# LedDimming.net
KiCad netlist of a schematic drawn in Altium Designer
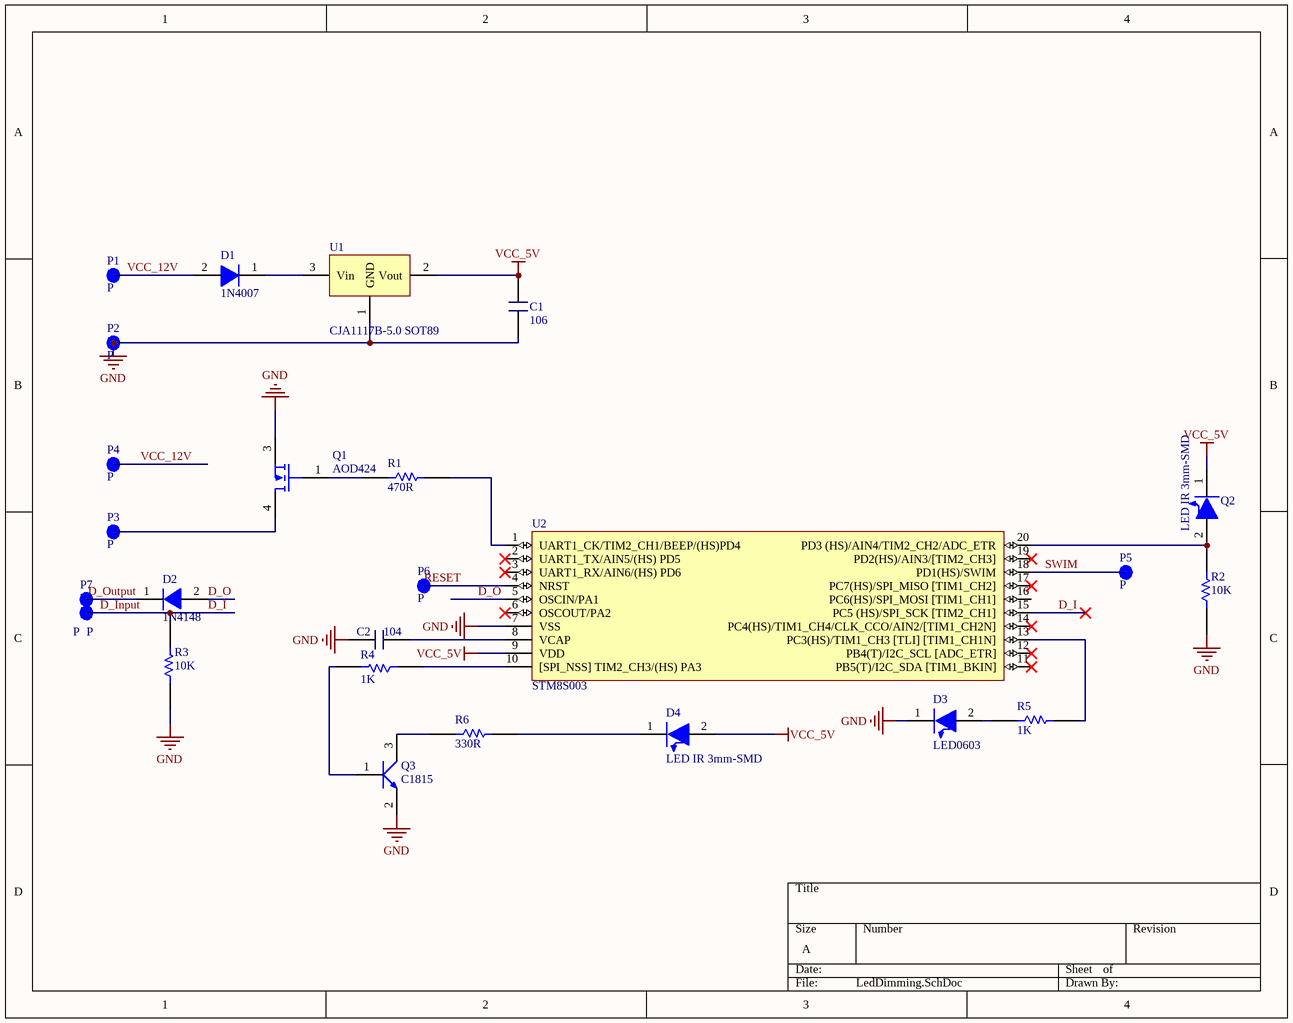
[diagram p0: LedDimming.SchDoc]

(export (version "E")
  (design (tool "Eeschema 10.0.6"))
  (components
    (comp (ref "C1")
      (value "106")
      (footprint "CAPC2012X12N")
      (libsource (lib "Integrated_Library1") (part "Capacitor 106"))
    )
    (comp (ref "C2")
      (value "104")
      (footprint "CAPC2012X12N")
      (libsource (lib "Integrated_Library1") (part "Capacitor 104 0603"))
    )
    (comp (ref "D1")
      (value "1N4007")
      (footprint "SODFL504X244-2N")
      (description "1N4007_SMD")
      (libsource (lib "Integrated_Library1") (part "1N4007_SMD Diode"))
    )
    (comp (ref "D2")
      (value "1N4148")
      (footprint "DIOMELF3515N")
      (description "DIODE GEN PURP 75V 200MA DO213AA")
      (libsource (lib "Integrated_Library1") (part "1N4148_SMD"))
    )
    (comp (ref "D3")
      (value "LED0603")
      (footprint "DIOC1608X06N")
      (libsource (lib "Integrated_Library1") (part "LED0603"))
    )
    (comp (ref "D4")
      (value "LED IR 3mm-SMD")
      (footprint "LED_IR_3mm-SMD")
      (libsource (lib "Integrated_Library1") (part "LED IR 3mm-SMD"))
    )
    (comp (ref "P1") (value "P") (footprint "Point") (libsource (lib "Integrated_Library1") (part "Point")))
    (comp (ref "P2") (value "P") (footprint "Point") (libsource (lib "Integrated_Library1") (part "Point")))
    (comp (ref "P3") (value "P") (footprint "Point") (libsource (lib "Integrated_Library1") (part "Point")))
    (comp (ref "P4") (value "P") (footprint "Point") (libsource (lib "Integrated_Library1") (part "Point")))
    (comp (ref "P5") (value "P") (footprint "Point") (libsource (lib "Integrated_Library1") (part "Point")))
    (comp (ref "P6") (value "P") (footprint "Point") (libsource (lib "Integrated_Library1") (part "Point")))
    (comp (ref "P7") (value "P") (footprint "Point") (libsource (lib "Integrated_Library1") (part "Point")))
    (comp (ref "P8") (value "P") (footprint "Point") (libsource (lib "Integrated_Library1") (part "Point")))
    (comp (ref "Q1")
      (value "AOD424")
      (footprint "DPAK228P991X229-3N_TO252")
      (description "AOD424 20V N-Channel MOSFET")
      (libsource (lib "Integrated_Library1") (part "AOD424 20V N-Channel MOSFET"))
    )
    (comp (ref "Q2")
      (value "LED IR 3mm-SMD")
      (footprint "LED_IR_3mm-SMD")
      (libsource (lib "Integrated_Library1") (part "LED IR 3mm-SMD"))
    )
    (comp (ref "Q3")
      (value "C1815")
      (footprint "SOT95P278X125-3N")
      (description "SOT-23 Plastic-Encapsulate Transistors")
      (libsource (lib "Integrated_Library1") (part "Transitor C1815 NPN"))
    )
    (comp (ref "R1")
      (value "470R")
      (footprint "RESC2608X06N_0603")
      (description "Thick Film Resistors - SMD 470 ohm 5%")
      (libsource (lib "Integrated_Library1") (part "R470_0603_5%"))
    )
    (comp (ref "R2")
      (value "10K")
      (footprint "RESC2608X06N_0603")
      (description "RES SMD 10K OHM 1% 1/4W 0603")
      (libsource (lib "Integrated_Library1") (part "R10k_0603_5%"))
    )
    (comp (ref "R3")
      (value "10K")
      (footprint "RESC2608X06N_0603")
      (description "RES SMD 10K OHM 1% 1/4W 0603")
      (libsource (lib "Integrated_Library1") (part "R10k_0603_5%"))
    )
    (comp (ref "R4")
      (value "1K")
      (footprint "RESC2608X06N_0603")
      (description "Thick Film Resistors - SMD 0603 1kOHMS 5% 1/10WATT")
      (libsource (lib "Integrated_Library1") (part "1k_0603_5%"))
    )
    (comp (ref "R5")
      (value "1K")
      (footprint "RESC2608X06N_0603")
      (description "Thick Film Resistors - SMD 0603 1kOHMS 5% 1/10WATT")
      (libsource (lib "Integrated_Library1") (part "1k_0603_5%"))
    )
    (comp (ref "R6")
      (value "330R")
      (footprint "RESC2608X06N_0603")
      (description "Thick Film Resistors - SMD 330 ohm 5%")
      (libsource (lib "Integrated_Library1") (part "R330_0603_5%"))
    )
    (comp (ref "U1")
      (value "CJA1117B-5.0 SOT89")
      (footprint "SOT89-150P409X160-3N")
      (description "CJA1117B-5.0 SOT89 Power IC 1A 5V_IC")
      (libsource (lib "Integrated_Library1") (part "CJA1117B-5.0 SOT89"))
    )
    (comp (ref "U2")
      (value "STM8S003")
      (footprint "TSOP65P640X120-20N")
      (description "MCU 8-bit STM8S STM8 CISC 8KB Flash 3.3V/5V 20-Pin TSSOP T/R")
      (libsource (lib "Integrated_Library1") (part "STM8S003"))
    )
  )
  (nets
    (net (code "1") (name "/D_I") (class "Default")
      (node (ref "P8") (pin "1") (pinfunction "1_1") (pintype "passive"))
      (node (ref "R3") (pin "2") (pinfunction "2_2") (pintype "passive"))
      (node (ref "U2") (pin "15") (pinfunction "PC5_(HS)/SPI_SCK_[TIM2_CH1]_15") (pintype "bidirectional"))
    )
    (net (code "2") (name "/D_O") (class "Default")
      (node (ref "D2") (pin "2") (pinfunction "A_2") (pintype "passive"))
      (node (ref "U2") (pin "5") (pinfunction "OSCIN/PA1_5") (pintype "bidirectional"))
    )
    (net (code "3") (name "/D_Output") (class "Default")
      (node (ref "D2") (pin "1") (pinfunction "C_1") (pintype "passive"))
      (node (ref "P7") (pin "1") (pinfunction "1_1") (pintype "passive"))
    )
    (net (code "4") (name "/RESET") (class "Default")
      (node (ref "P6") (pin "1") (pinfunction "1_1") (pintype "passive"))
      (node (ref "U2") (pin "4") (pinfunction "NRST_4") (pintype "bidirectional"))
    )
    (net (code "5") (name "/SWIM") (class "Default")
      (node (ref "P5") (pin "1") (pinfunction "1_1") (pintype "passive"))
      (node (ref "U2") (pin "18") (pinfunction "PD1(HS)/SWIM_18") (pintype "bidirectional"))
    )
    (net (code "6") (name "/VCC_12V") (class "Default")
      (node (ref "D1") (pin "2") (pinfunction "A_2") (pintype "passive"))
      (node (ref "P1") (pin "1") (pinfunction "1_1") (pintype "passive"))
      (node (ref "P4") (pin "1") (pinfunction "1_1") (pintype "passive"))
    )
    (net (code "7") (name "GND") (class "Default")
      (node (ref "C1") (pin "1") (pinfunction "1_1") (pintype "passive"))
      (node (ref "C2") (pin "1") (pinfunction "1_1") (pintype "passive"))
      (node (ref "D3") (pin "1") (pinfunction "A_1") (pintype "passive"))
      (node (ref "P2") (pin "1") (pinfunction "1_1") (pintype "passive"))
      (node (ref "Q1") (pin "3") (pinfunction "S_3") (pintype "passive"))
      (node (ref "Q3") (pin "2") (pinfunction "E_2") (pintype "passive"))
      (node (ref "R2") (pin "1") (pinfunction "1_1") (pintype "passive"))
      (node (ref "R3") (pin "1") (pinfunction "1_1") (pintype "passive"))
      (node (ref "U1") (pin "1") (pinfunction "GND_1") (pintype "power_in"))
      (node (ref "U2") (pin "7") (pinfunction "VSS_7") (pintype "power_in"))
    )
    (net (code "8") (name "Net-(D1-C)") (class "Default")
      (node (ref "D1") (pin "1") (pinfunction "C_1") (pintype "passive"))
      (node (ref "U1") (pin "3") (pinfunction "Vin_3") (pintype "power_in"))
    )
    (net (code "9") (name "Net-(D3-C)") (class "Default")
      (node (ref "D3") (pin "2") (pinfunction "C_2") (pintype "passive"))
      (node (ref "R5") (pin "1") (pinfunction "1_1") (pintype "passive"))
    )
    (net (code "10") (name "Net-(D4-A)") (class "Default")
      (node (ref "D4") (pin "1") (pinfunction "A_1") (pintype "passive"))
      (node (ref "R6") (pin "2") (pinfunction "2_2") (pintype "passive"))
    )
    (net (code "11") (name "Net-(Q1-D)") (class "Default")
      (node (ref "P3") (pin "1") (pinfunction "1_1") (pintype "passive"))
      (node (ref "Q1") (pin "4") (pinfunction "D_4") (pintype "passive"))
    )
    (net (code "12") (name "Net-(Q1-G)") (class "Default")
      (node (ref "Q1") (pin "1") (pinfunction "G_1") (pintype "passive"))
      (node (ref "R1") (pin "1") (pinfunction "1_1") (pintype "passive"))
    )
    (net (code "13") (name "Net-(Q2-C)") (class "Default")
      (node (ref "Q2") (pin "2") (pinfunction "C_2") (pintype "passive"))
      (node (ref "R2") (pin "2") (pinfunction "2_2") (pintype "passive"))
      (node (ref "U2") (pin "20") (pinfunction "PD3_(HS)/AIN4/TIM2_CH2/ADC_ETR_20") (pintype "bidirectional"))
    )
    (net (code "14") (name "Net-(Q3-B)") (class "Default")
      (node (ref "Q3") (pin "1") (pinfunction "B_1") (pintype "passive"))
      (node (ref "R4") (pin "2") (pinfunction "2_2") (pintype "passive"))
    )
    (net (code "15") (name "Net-(Q3-C)") (class "Default")
      (node (ref "Q3") (pin "3") (pinfunction "C_3") (pintype "passive"))
      (node (ref "R6") (pin "1") (pinfunction "1_1") (pintype "passive"))
    )
    (net (code "16") (name "Net-(U2-PC3(HS){slash}TIM1_CH3_[TLI]_[TIM1_CH1N])") (class "Default")
      (node (ref "R5") (pin "2") (pinfunction "2_2") (pintype "passive"))
      (node (ref "U2") (pin "13") (pinfunction "PC3(HS)/TIM1_CH3_[TLI]_[TIM1_CH1N]_13") (pintype "bidirectional"))
    )
    (net (code "17") (name "Net-(U2-UART1_CK{slash}TIM2_CH1{slash}BEEP{slash}(HS)PD4)") (class "Default")
      (node (ref "R1") (pin "2") (pinfunction "2_2") (pintype "passive"))
      (node (ref "U2") (pin "1") (pinfunction "UART1_CK/TIM2_CH1/BEEP/(HS)PD4_1") (pintype "bidirectional"))
    )
    (net (code "18") (name "Net-(U2-VCAP)") (class "Default")
      (node (ref "C2") (pin "2") (pinfunction "2_2") (pintype "passive"))
      (node (ref "U2") (pin "8") (pinfunction "VCAP_8") (pintype "power_in"))
    )
    (net (code "19") (name "Net-(U2-[SPI_NSS]_TIM2_CH3{slash}(HS)_PA3)") (class "Default")
      (node (ref "R4") (pin "1") (pinfunction "1_1") (pintype "passive"))
      (node (ref "U2") (pin "10") (pinfunction "[SPI_NSS]_TIM2_CH3/(HS)_PA3_10") (pintype "power_in"))
    )
    (net (code "20") (name "VCC_5V") (class "Default")
      (node (ref "C1") (pin "2") (pinfunction "2_2") (pintype "passive"))
      (node (ref "D4") (pin "2") (pinfunction "C_2") (pintype "passive"))
      (node (ref "Q2") (pin "1") (pinfunction "A_1") (pintype "passive"))
      (node (ref "U1") (pin "2") (pinfunction "Vout_2") (pintype "power_in"))
      (node (ref "U2") (pin "9") (pinfunction "VDD_9") (pintype "power_in"))
    )
    (net (code "21") (name "unconnected-(U2-OSCOUT{slash}PA2-Pad6)") (class "Default")
      (node (ref "U2") (pin "6") (pinfunction "OSCOUT/PA2_6") (pintype "bidirectional+no_connect"))
    )
    (net (code "22") (name "unconnected-(U2-PB4(T){slash}I2C_SCL_[ADC_ETR]-Pad12)") (class "Default")
      (node (ref "U2") (pin "12") (pinfunction "PB4(T)/I2C_SCL_[ADC_ETR]_12") (pintype "bidirectional+no_connect"))
    )
    (net (code "23") (name "unconnected-(U2-PB5(T){slash}I2C_SDA_[TIM1_BKIN]-Pad11)") (class "Default")
      (node (ref "U2") (pin "11") (pinfunction "PB5(T)/I2C_SDA_[TIM1_BKIN]_11") (pintype "bidirectional+no_connect"))
    )
    (net (code "24") (name "unconnected-(U2-PC4(HS){slash}TIM1_CH4{slash}CLK_CCO{slash}AIN2{slash}[TIM1_CH2N]-Pad14)") (class "Default")
      (node (ref "U2") (pin "14") (pinfunction "PC4(HS)/TIM1_CH4/CLK_CCO/AIN2/[TIM1_CH2N]_14") (pintype "bidirectional+no_connect"))
    )
    (net (code "25") (name "unconnected-(U2-PC6(HS){slash}SPI_MOSI_[TIM1_CH1]-Pad16)") (class "Default")
      (node (ref "U2") (pin "16") (pinfunction "PC6(HS)/SPI_MOSI_[TIM1_CH1]_16") (pintype "bidirectional"))
    )
    (net (code "26") (name "unconnected-(U2-PC7(HS){slash}SPI_MISO_[TIM1_CH2]-Pad17)") (class "Default")
      (node (ref "U2") (pin "17") (pinfunction "PC7(HS)/SPI_MISO_[TIM1_CH2]_17") (pintype "bidirectional+no_connect"))
    )
    (net (code "27") (name "unconnected-(U2-PD2(HS){slash}AIN3{slash}[TIM2_CH3]-Pad19)") (class "Default")
      (node (ref "U2") (pin "19") (pinfunction "PD2(HS)/AIN3/[TIM2_CH3]_19") (pintype "bidirectional+no_connect"))
    )
    (net (code "28") (name "unconnected-(U2-UART1_RX{slash}AIN6{slash}(HS)_PD6-Pad3)") (class "Default")
      (node (ref "U2") (pin "3") (pinfunction "UART1_RX/AIN6/(HS)_PD6_3") (pintype "bidirectional+no_connect"))
    )
    (net (code "29") (name "unconnected-(U2-UART1_TX{slash}AIN5{slash}(HS)_PD5-Pad2)") (class "Default")
      (node (ref "U2") (pin "2") (pinfunction "UART1_TX/AIN5/(HS)_PD5_2") (pintype "bidirectional+no_connect"))
    )
  )
)
